# 1_Power.net
KiCad netlist of a schematic drawn in Altium Designer
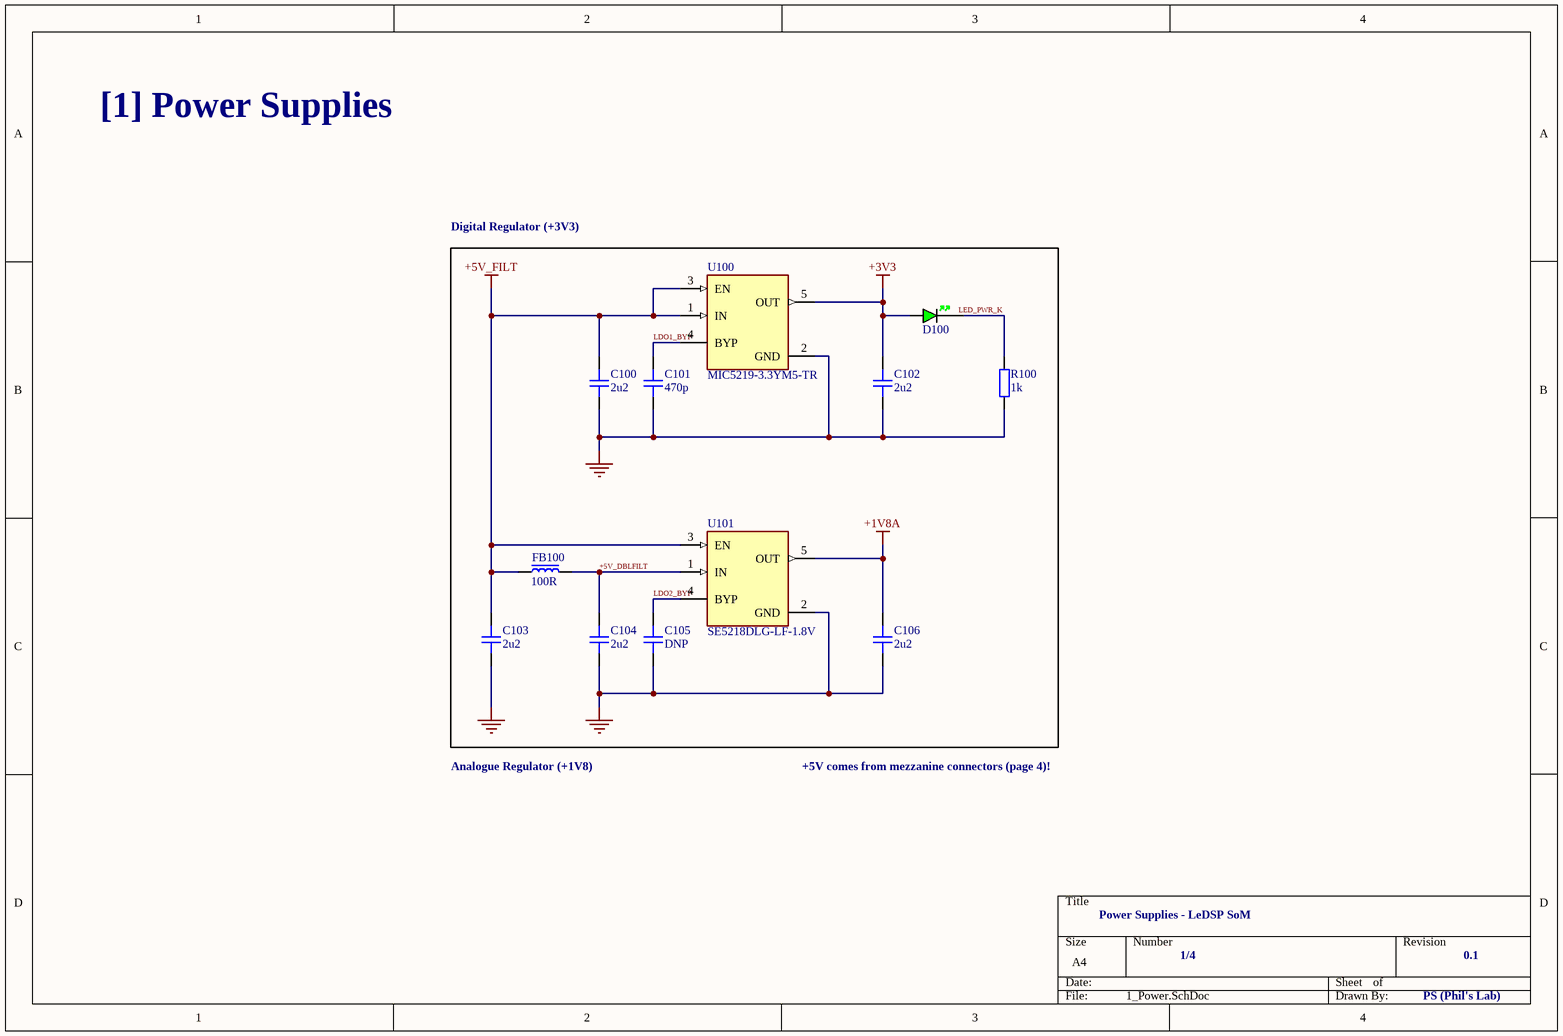
[diagram p0: 1_Power.SchDoc]

(export (version "E")
  (design (tool "Eeschema 10.0.6"))
  (components
    (comp (ref "C100")
      (value "2u2")
      (footprint "CAP_0603")
      (description "Capacitor SMD 0603 16V")
      (libsource (lib "Schematic-Lib-PhilsLab") (part "CAP_0603_16V"))
    )
    (comp (ref "C101")
      (value "470p")
      (footprint "CAP_0402")
      (description "Capacitor SMD 0402 16V")
      (libsource (lib "Schematic-Lib-PhilsLab") (part "CAP_0402_16V"))
    )
    (comp (ref "C102")
      (value "2u2")
      (footprint "CAP_0603")
      (description "Capacitor SMD 0603 16V")
      (libsource (lib "Schematic-Lib-PhilsLab") (part "CAP_0603_16V"))
    )
    (comp (ref "C103")
      (value "2u2")
      (footprint "CAP_0603")
      (description "Capacitor SMD 0603 16V")
      (libsource (lib "Schematic-Lib-PhilsLab") (part "CAP_0603_16V"))
    )
    (comp (ref "C104")
      (value "2u2")
      (footprint "CAP_0603")
      (description "Capacitor SMD 0603 16V")
      (libsource (lib "Schematic-Lib-PhilsLab") (part "CAP_0603_16V"))
    )
    (comp (ref "C105")
      (value "DNP")
      (footprint "CAP_0402")
      (description "Capacitor SMD 0402 16V")
      (libsource (lib "Schematic-Lib-PhilsLab") (part "CAP_0402_16V"))
    )
    (comp (ref "C106")
      (value "2u2")
      (footprint "CAP_0603")
      (description "Capacitor SMD 0603 16V")
      (libsource (lib "Schematic-Lib-PhilsLab") (part "CAP_0603_16V"))
    )
    (comp (ref "D100")
      (value "GREEN")
      (footprint "LED_0402_GREEN")
      (description "LED 0402 GREEN SMD")
      (libsource (lib "Schematic-Lib-PhilsLab") (part "LED_0402_GREEN"))
    )
    (comp (ref "FB100")
      (value "100R")
      (footprint "FB_0603")
      (description "Ferrite Bead SMD 0603")
      (libsource (lib "Schematic-Lib-PhilsLab") (part "FB_0603"))
    )
    (comp (ref "R100")
      (value "1k")
      (footprint "RES_0402")
      (description "Resistor SMD 0402")
      (libsource (lib "Schematic-Lib-PhilsLab") (part "RES_0402"))
    )
    (comp (ref "U100")
      (value "MIC5219-3.3YM5-TR")
      (footprint "FP-SOT23-5LD-PL-1-IPC_A")
      (description "IC REG LINEAR 3.3V 500MA SOT23-5")
      (libsource (lib "Altium Content Vault") (part "16b36b16d6b7b40c29ab14718bc3058"))
    )
    (comp (ref "U101")
      (value "SE5218DLG-LF-1.8V")
      (footprint "FP-SOT23-5LD-PL-1-IPC_A")
      (description "IC REG LINEAR 3.3V 500MA SOT23-5")
      (libsource (lib "Altium Content Vault") (part "16b36b16d6b7b40c29ab14718bc3058"))
    )
  )
  (nets
    (net (code "1") (name "+1V8A") (class "Default")
      (node (ref "C106") (pin "2") (pinfunction "2_2") (pintype "passive"))
      (node (ref "U101") (pin "5") (pinfunction "OUT_5") (pintype "output"))
    )
    (net (code "2") (name "+3V3") (class "Default")
      (node (ref "C102") (pin "2") (pinfunction "2_2") (pintype "passive"))
      (node (ref "D100") (pin "A") (pinfunction "A_A") (pintype "passive"))
      (node (ref "U100") (pin "5") (pinfunction "OUT_5") (pintype "output"))
    )
    (net (code "3") (name "+5V_FILT") (class "Default")
      (node (ref "C100") (pin "2") (pinfunction "2_2") (pintype "passive"))
      (node (ref "C103") (pin "2") (pinfunction "2_2") (pintype "passive"))
      (node (ref "FB100") (pin "1") (pinfunction "1_1") (pintype "passive"))
      (node (ref "U100") (pin "1") (pinfunction "IN_1") (pintype "input"))
      (node (ref "U100") (pin "3") (pinfunction "EN_3") (pintype "input"))
      (node (ref "U101") (pin "3") (pinfunction "EN_3") (pintype "input"))
    )
    (net (code "4") (name "/+5V_DBLFILT") (class "Default")
      (node (ref "C104") (pin "2") (pinfunction "2_2") (pintype "passive"))
      (node (ref "FB100") (pin "2") (pinfunction "2_2") (pintype "passive"))
      (node (ref "U101") (pin "1") (pinfunction "IN_1") (pintype "input"))
    )
    (net (code "5") (name "/LDO1_BYP") (class "Default")
      (node (ref "C101") (pin "2") (pinfunction "2_2") (pintype "passive"))
      (node (ref "U100") (pin "4") (pinfunction "BYP_4") (pintype "passive"))
    )
    (net (code "6") (name "/LDO2_BYP") (class "Default")
      (node (ref "C105") (pin "2") (pinfunction "2_2") (pintype "passive"))
      (node (ref "U101") (pin "4") (pinfunction "BYP_4") (pintype "passive"))
    )
    (net (code "7") (name "/LED_PWR_K") (class "Default")
      (node (ref "D100") (pin "K") (pinfunction "K_K") (pintype "passive"))
      (node (ref "R100") (pin "2") (pinfunction "2_2") (pintype "passive"))
    )
    (net (code "8") (name "GND") (class "Default")
      (node (ref "C100") (pin "1") (pinfunction "1_1") (pintype "passive"))
      (node (ref "C101") (pin "1") (pinfunction "1_1") (pintype "passive"))
      (node (ref "C102") (pin "1") (pinfunction "1_1") (pintype "passive"))
      (node (ref "C103") (pin "1") (pinfunction "1_1") (pintype "passive"))
      (node (ref "C104") (pin "1") (pinfunction "1_1") (pintype "passive"))
      (node (ref "C105") (pin "1") (pinfunction "1_1") (pintype "passive"))
      (node (ref "C106") (pin "1") (pinfunction "1_1") (pintype "passive"))
      (node (ref "R100") (pin "1") (pinfunction "1_1") (pintype "passive"))
      (node (ref "U100") (pin "2") (pinfunction "GND_2") (pintype "power_in"))
      (node (ref "U101") (pin "2") (pinfunction "GND_2") (pintype "power_in"))
    )
  )
)
